# AvrProgrammerSchematic.net
KiCad netlist of a schematic drawn in EAGLE
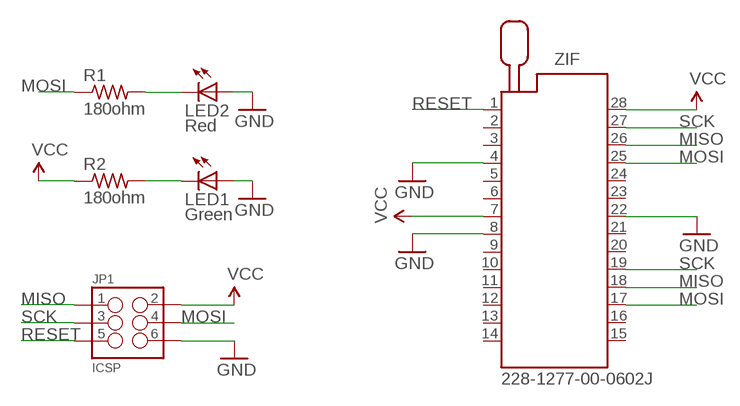
[diagram p0: schematic, sheet 1]

(export (version "E")
  (design (tool "Eeschema 10.0.6"))
  (components
    (comp (ref "JP1")
      (value "ICSP")
      (footprint "eagle-import:2X3_SMD")
      (libsource (lib "eagle-import") (part "M03X2"))
    )
    (comp (ref "LED1")
      (value "Green")
      (footprint "eagle-import:LED3MM")
      (libsource (lib "eagle-import") (part "LED3MM"))
    )
    (comp (ref "LED2")
      (value "Red")
      (footprint "eagle-import:LED3MM")
      (libsource (lib "eagle-import") (part "LED3MM"))
    )
    (comp (ref "R1")
      (value "180ohm")
      (footprint "eagle-import:0207_7")
      (libsource (lib "eagle-import") (part "R-US_0207/7"))
    )
    (comp (ref "R2")
      (value "180ohm")
      (footprint "eagle-import:0207_7")
      (libsource (lib "eagle-import") (part "R-US_0207/7"))
    )
    (comp (ref "ZIF")
      (value "228-1277-00-0602J")
      (footprint "eagle-import:228-1277-00-0602J")
      (fields (field (name "MF") "3M"))
      (libsource (lib "eagle-import") (part "228-?00-0602J1277-"))
    )
  )
  (nets
    (net (code "1") (name "/MISO") (class "Default")
      (node (ref "JP1") (pin "1") (pinfunction "1_1") (pintype "bidirectional"))
      (node (ref "ZIF") (pin "18") (pinfunction "18_18") (pintype "passive"))
      (node (ref "ZIF") (pin "26") (pinfunction "26_26") (pintype "passive"))
    )
    (net (code "2") (name "/MOSI") (class "Default")
      (node (ref "JP1") (pin "4") (pinfunction "4_4") (pintype "bidirectional"))
      (node (ref "R1") (pin "1") (pinfunction "1_1") (pintype "passive"))
      (node (ref "ZIF") (pin "17") (pinfunction "17_17") (pintype "passive"))
      (node (ref "ZIF") (pin "25") (pinfunction "25_25") (pintype "passive"))
    )
    (net (code "3") (name "/RESET") (class "Default")
      (node (ref "JP1") (pin "5") (pinfunction "5_5") (pintype "bidirectional"))
      (node (ref "ZIF") (pin "1") (pinfunction "1_1") (pintype "passive"))
    )
    (net (code "4") (name "/SCK") (class "Default")
      (node (ref "JP1") (pin "3") (pinfunction "3_3") (pintype "bidirectional"))
      (node (ref "ZIF") (pin "19") (pinfunction "19_19") (pintype "passive"))
      (node (ref "ZIF") (pin "27") (pinfunction "27_27") (pintype "passive"))
    )
    (net (code "5") (name "GND") (class "Default")
      (node (ref "JP1") (pin "6") (pinfunction "6_6") (pintype "bidirectional"))
      (node (ref "LED1") (pin "A") (pinfunction "A_A") (pintype "passive"))
      (node (ref "LED2") (pin "A") (pinfunction "A_A") (pintype "passive"))
      (node (ref "ZIF") (pin "22") (pinfunction "22_22") (pintype "passive"))
      (node (ref "ZIF") (pin "4") (pinfunction "4_4") (pintype "passive"))
      (node (ref "ZIF") (pin "8") (pinfunction "8_8") (pintype "passive"))
    )
    (net (code "6") (name "Net-(LED1-C)") (class "Default")
      (node (ref "LED1") (pin "K") (pinfunction "C_K") (pintype "passive"))
      (node (ref "R2") (pin "2") (pinfunction "2_2") (pintype "passive"))
    )
    (net (code "7") (name "Net-(LED2-C)") (class "Default")
      (node (ref "LED2") (pin "K") (pinfunction "C_K") (pintype "passive"))
      (node (ref "R1") (pin "2") (pinfunction "2_2") (pintype "passive"))
    )
    (net (code "8") (name "VCC") (class "Default")
      (node (ref "JP1") (pin "2") (pinfunction "2_2") (pintype "bidirectional"))
      (node (ref "R2") (pin "1") (pinfunction "1_1") (pintype "passive"))
      (node (ref "ZIF") (pin "28") (pinfunction "28_28") (pintype "passive"))
      (node (ref "ZIF") (pin "7") (pinfunction "7_7") (pintype "passive"))
    )
    (net (code "9") (name "unconnected-(ZIF-Pad2)") (class "Default")
      (node (ref "ZIF") (pin "2") (pinfunction "2_2") (pintype "passive"))
    )
    (net (code "10") (name "unconnected-(ZIF-Pad3)") (class "Default")
      (node (ref "ZIF") (pin "3") (pinfunction "3_3") (pintype "passive"))
    )
    (net (code "11") (name "unconnected-(ZIF-Pad5)") (class "Default")
      (node (ref "ZIF") (pin "5") (pinfunction "5_5") (pintype "passive"))
    )
    (net (code "12") (name "unconnected-(ZIF-Pad6)") (class "Default")
      (node (ref "ZIF") (pin "6") (pinfunction "6_6") (pintype "passive"))
    )
    (net (code "13") (name "unconnected-(ZIF-Pad9)") (class "Default")
      (node (ref "ZIF") (pin "9") (pinfunction "9_9") (pintype "passive"))
    )
    (net (code "14") (name "unconnected-(ZIF-Pad10)") (class "Default")
      (node (ref "ZIF") (pin "10") (pinfunction "10_10") (pintype "passive"))
    )
    (net (code "15") (name "unconnected-(ZIF-Pad11)") (class "Default")
      (node (ref "ZIF") (pin "11") (pinfunction "11_11") (pintype "passive"))
    )
    (net (code "16") (name "unconnected-(ZIF-Pad12)") (class "Default")
      (node (ref "ZIF") (pin "12") (pinfunction "12_12") (pintype "passive"))
    )
    (net (code "17") (name "unconnected-(ZIF-Pad13)") (class "Default")
      (node (ref "ZIF") (pin "13") (pinfunction "13_13") (pintype "passive"))
    )
    (net (code "18") (name "unconnected-(ZIF-Pad14)") (class "Default")
      (node (ref "ZIF") (pin "14") (pinfunction "14_14") (pintype "passive"))
    )
    (net (code "19") (name "unconnected-(ZIF-Pad15)") (class "Default")
      (node (ref "ZIF") (pin "15") (pinfunction "15_15") (pintype "passive"))
    )
    (net (code "20") (name "unconnected-(ZIF-Pad16)") (class "Default")
      (node (ref "ZIF") (pin "16") (pinfunction "16_16") (pintype "passive"))
    )
    (net (code "21") (name "unconnected-(ZIF-Pad20)") (class "Default")
      (node (ref "ZIF") (pin "20") (pinfunction "20_20") (pintype "passive"))
    )
    (net (code "22") (name "unconnected-(ZIF-Pad21)") (class "Default")
      (node (ref "ZIF") (pin "21") (pinfunction "21_21") (pintype "passive"))
    )
    (net (code "23") (name "unconnected-(ZIF-Pad23)") (class "Default")
      (node (ref "ZIF") (pin "23") (pinfunction "23_23") (pintype "passive"))
    )
    (net (code "24") (name "unconnected-(ZIF-Pad24)") (class "Default")
      (node (ref "ZIF") (pin "24") (pinfunction "24_24") (pintype "passive"))
    )
  )
)
